# catch_sensor.net
KiCad netlist of a schematic drawn in EAGLE
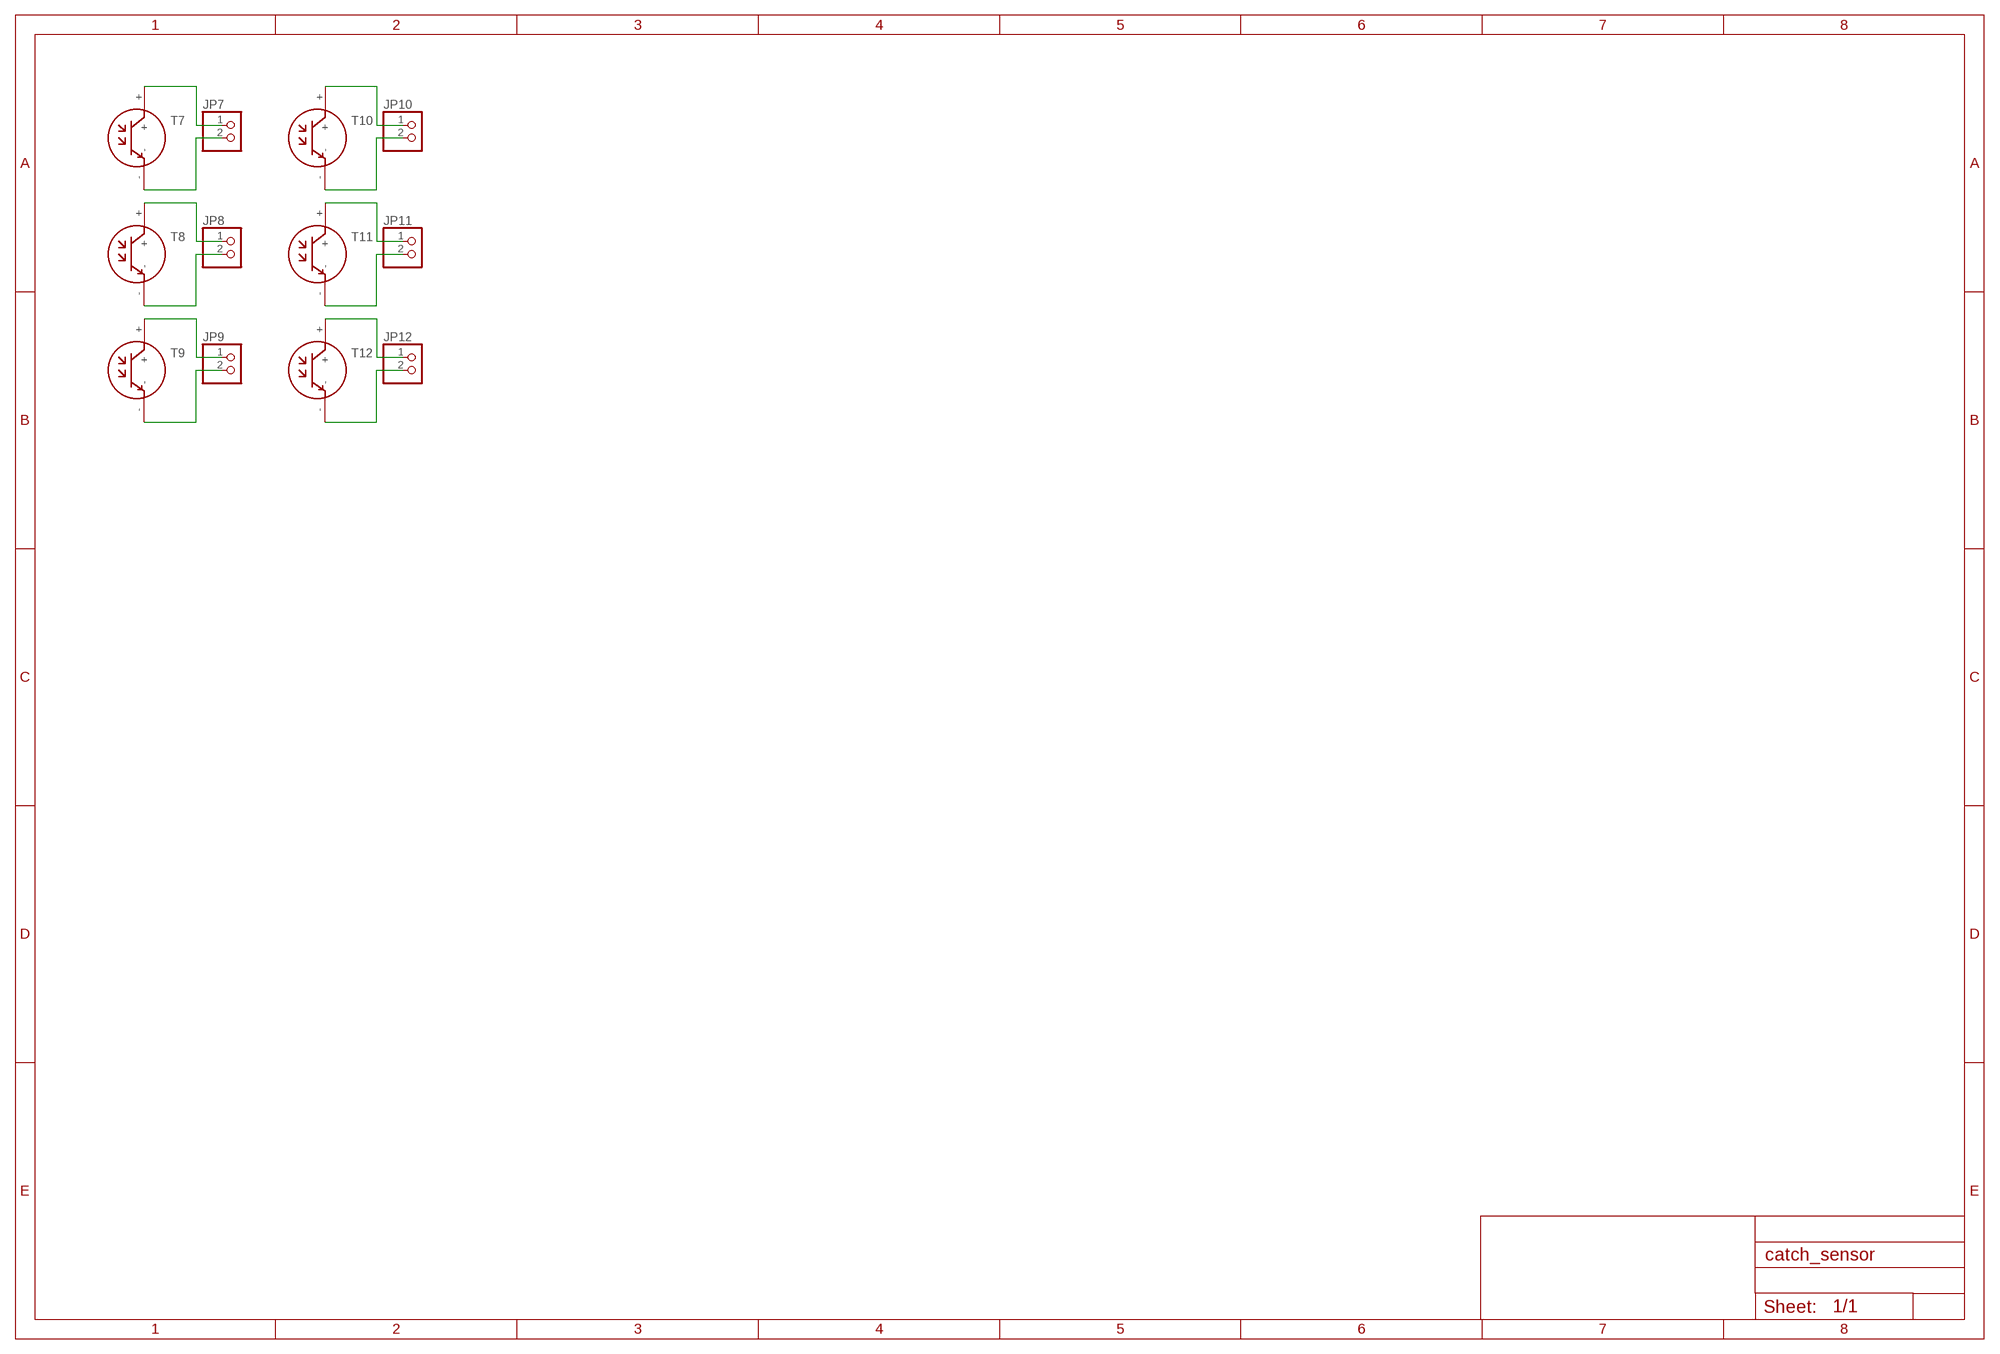
[diagram p0: schematic, sheet 1]

(export (version "E")
  (design (tool "Eeschema 10.0.6"))
  (components
    (comp (ref "JP7")
      (value "PINHD-1X2")
      (footprint "eagle-import:1X02")
      (libsource (lib "eagle-import") (part "PINHD-1X2"))
    )
    (comp (ref "JP8")
      (value "PINHD-1X2")
      (footprint "eagle-import:1X02")
      (libsource (lib "eagle-import") (part "PINHD-1X2"))
    )
    (comp (ref "JP9")
      (value "PINHD-1X2")
      (footprint "eagle-import:1X02")
      (libsource (lib "eagle-import") (part "PINHD-1X2"))
    )
    (comp (ref "JP10")
      (value "PINHD-1X2")
      (footprint "eagle-import:1X02")
      (libsource (lib "eagle-import") (part "PINHD-1X2"))
    )
    (comp (ref "JP11")
      (value "PINHD-1X2")
      (footprint "eagle-import:1X02")
      (libsource (lib "eagle-import") (part "PINHD-1X2"))
    )
    (comp (ref "JP12")
      (value "PINHD-1X2")
      (footprint "eagle-import:1X02")
      (libsource (lib "eagle-import") (part "PINHD-1X2"))
    )
    (comp (ref "T7")
      (value "NJL7302L-F3")
      (footprint "eagle-import:NJL7302L-F3")
      (libsource (lib "eagle-import") (part "NJL7302L-F3"))
    )
    (comp (ref "T8")
      (value "NJL7302L-F3")
      (footprint "eagle-import:NJL7302L-F3")
      (libsource (lib "eagle-import") (part "NJL7302L-F3"))
    )
    (comp (ref "T9")
      (value "NJL7302L-F3")
      (footprint "eagle-import:NJL7302L-F3")
      (libsource (lib "eagle-import") (part "NJL7302L-F3"))
    )
    (comp (ref "T10")
      (value "NJL7302L-F3")
      (footprint "eagle-import:NJL7302L-F3")
      (libsource (lib "eagle-import") (part "NJL7302L-F3"))
    )
    (comp (ref "T11")
      (value "NJL7302L-F3")
      (footprint "eagle-import:NJL7302L-F3")
      (libsource (lib "eagle-import") (part "NJL7302L-F3"))
    )
    (comp (ref "T12")
      (value "NJL7302L-F3")
      (footprint "eagle-import:NJL7302L-F3")
      (libsource (lib "eagle-import") (part "NJL7302L-F3"))
    )
  )
  (nets
    (net (code "1") (name "Net-(JP7-Pad1)") (class "Default")
      (node (ref "JP7") (pin "1") (pinfunction "1_1") (pintype "passive"))
      (node (ref "T7") (pin "+") (pinfunction "+_+") (pintype "bidirectional"))
    )
    (net (code "2") (name "Net-(JP7-Pad2)") (class "Default")
      (node (ref "JP7") (pin "2") (pinfunction "2_2") (pintype "passive"))
      (node (ref "T7") (pin "-") (pinfunction "-_-") (pintype "bidirectional"))
    )
    (net (code "3") (name "Net-(JP8-Pad1)") (class "Default")
      (node (ref "JP8") (pin "1") (pinfunction "1_1") (pintype "passive"))
      (node (ref "T8") (pin "+") (pinfunction "+_+") (pintype "bidirectional"))
    )
    (net (code "4") (name "Net-(JP8-Pad2)") (class "Default")
      (node (ref "JP8") (pin "2") (pinfunction "2_2") (pintype "passive"))
      (node (ref "T8") (pin "-") (pinfunction "-_-") (pintype "bidirectional"))
    )
    (net (code "5") (name "Net-(JP9-Pad1)") (class "Default")
      (node (ref "JP9") (pin "1") (pinfunction "1_1") (pintype "passive"))
      (node (ref "T9") (pin "+") (pinfunction "+_+") (pintype "bidirectional"))
    )
    (net (code "6") (name "Net-(JP9-Pad2)") (class "Default")
      (node (ref "JP9") (pin "2") (pinfunction "2_2") (pintype "passive"))
      (node (ref "T9") (pin "-") (pinfunction "-_-") (pintype "bidirectional"))
    )
    (net (code "7") (name "Net-(JP10-Pad1)") (class "Default")
      (node (ref "JP10") (pin "1") (pinfunction "1_1") (pintype "passive"))
      (node (ref "T10") (pin "+") (pinfunction "+_+") (pintype "bidirectional"))
    )
    (net (code "8") (name "Net-(JP10-Pad2)") (class "Default")
      (node (ref "JP10") (pin "2") (pinfunction "2_2") (pintype "passive"))
      (node (ref "T10") (pin "-") (pinfunction "-_-") (pintype "bidirectional"))
    )
    (net (code "9") (name "Net-(JP11-Pad1)") (class "Default")
      (node (ref "JP11") (pin "1") (pinfunction "1_1") (pintype "passive"))
      (node (ref "T11") (pin "+") (pinfunction "+_+") (pintype "bidirectional"))
    )
    (net (code "10") (name "Net-(JP11-Pad2)") (class "Default")
      (node (ref "JP11") (pin "2") (pinfunction "2_2") (pintype "passive"))
      (node (ref "T11") (pin "-") (pinfunction "-_-") (pintype "bidirectional"))
    )
    (net (code "11") (name "Net-(JP12-Pad1)") (class "Default")
      (node (ref "JP12") (pin "1") (pinfunction "1_1") (pintype "passive"))
      (node (ref "T12") (pin "+") (pinfunction "+_+") (pintype "bidirectional"))
    )
    (net (code "12") (name "Net-(JP12-Pad2)") (class "Default")
      (node (ref "JP12") (pin "2") (pinfunction "2_2") (pintype "passive"))
      (node (ref "T12") (pin "-") (pinfunction "-_-") (pintype "bidirectional"))
    )
  )
)
